# G850X.net
KiCad netlist of a schematic drawn in EAGLE
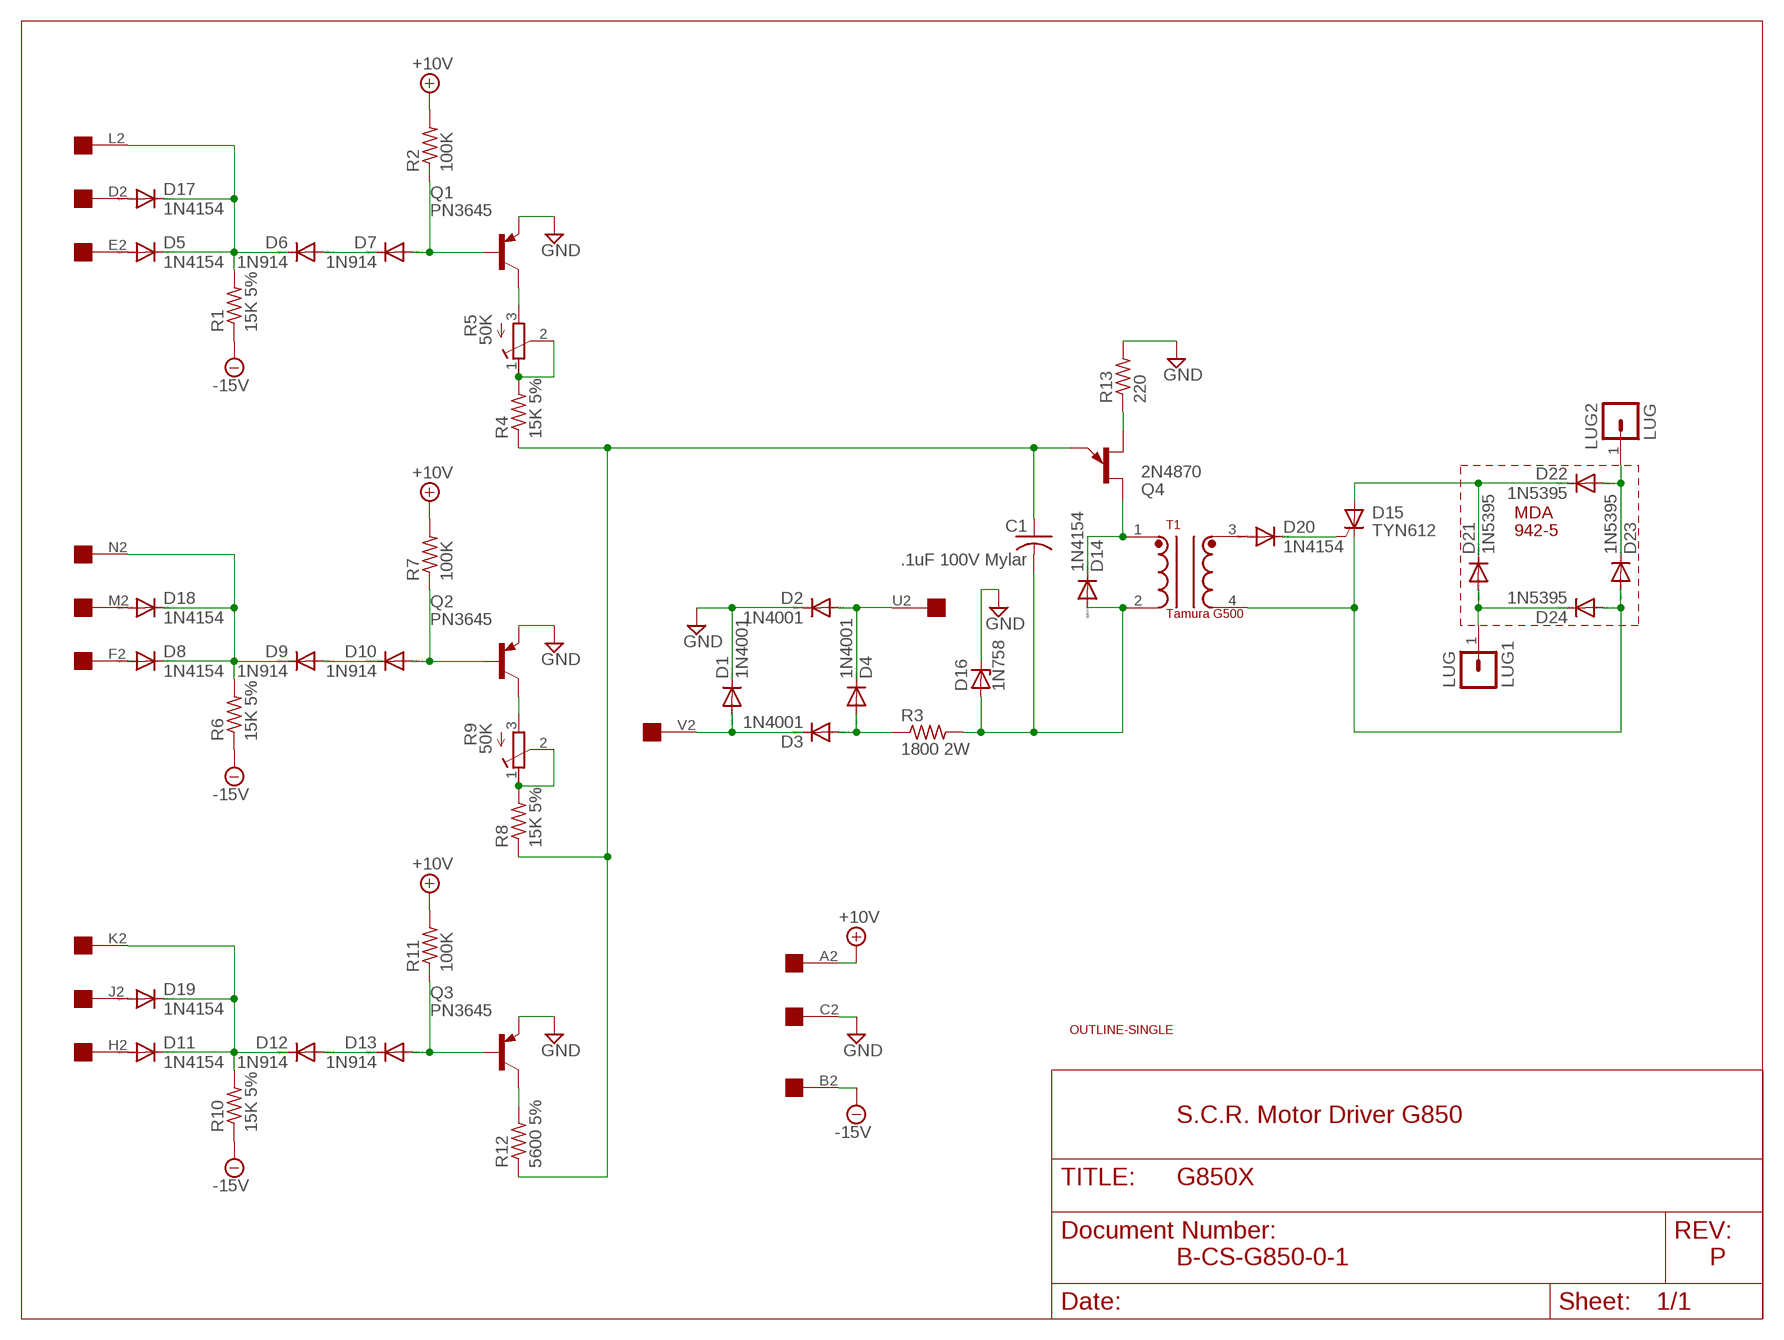
[diagram p0: schematic, sheet 1]

(export (version "E")
  (design (tool "Eeschema 10.0.6"))
  (components
    (comp (ref "C1")
      (value ".1uF 100V Mylar")
      (footprint "eagle-import:C275-093X316")
      (libsource (lib "eagle-import") (part "C-US275-093X316"))
    )
    (comp (ref "D1")
      (value "1N4001")
      (footprint "eagle-import:DO41-10")
      (libsource (lib "eagle-import") (part "1N4004"))
    )
    (comp (ref "D2")
      (value "1N4001")
      (footprint "eagle-import:DO41-10")
      (libsource (lib "eagle-import") (part "1N4004"))
    )
    (comp (ref "D3")
      (value "1N4001")
      (footprint "eagle-import:DO41-10")
      (libsource (lib "eagle-import") (part "1N4004"))
    )
    (comp (ref "D4")
      (value "1N4001")
      (footprint "eagle-import:DO41-10")
      (libsource (lib "eagle-import") (part "1N4004"))
    )
    (comp (ref "D5")
      (value "1N4154")
      (footprint "eagle-import:DO35-10")
      (libsource (lib "eagle-import") (part "1N4148DO35-10"))
    )
    (comp (ref "D6")
      (value "1N914")
      (footprint "eagle-import:DO35-10")
      (libsource (lib "eagle-import") (part "1N4148DO35-10"))
    )
    (comp (ref "D7")
      (value "1N914")
      (footprint "eagle-import:DO35-10")
      (libsource (lib "eagle-import") (part "1N4148DO35-10"))
    )
    (comp (ref "D8")
      (value "1N4154")
      (footprint "eagle-import:DO35-10")
      (libsource (lib "eagle-import") (part "1N4148DO35-10"))
    )
    (comp (ref "D9")
      (value "1N914")
      (footprint "eagle-import:DO35-10")
      (libsource (lib "eagle-import") (part "1N4148DO35-10"))
    )
    (comp (ref "D10")
      (value "1N914")
      (footprint "eagle-import:DO35-10")
      (libsource (lib "eagle-import") (part "1N4148DO35-10"))
    )
    (comp (ref "D11")
      (value "1N4154")
      (footprint "eagle-import:DO35-10")
      (libsource (lib "eagle-import") (part "1N4148DO35-10"))
    )
    (comp (ref "D12")
      (value "1N914")
      (footprint "eagle-import:DO35-10")
      (libsource (lib "eagle-import") (part "1N4148DO35-10"))
    )
    (comp (ref "D13")
      (value "1N914")
      (footprint "eagle-import:DO35-10")
      (libsource (lib "eagle-import") (part "1N4148DO35-10"))
    )
    (comp (ref "D14")
      (value "1N4154")
      (footprint "eagle-import:DO35-10")
      (libsource (lib "eagle-import") (part "1N4148DO35-10"))
    )
    (comp (ref "D15")
      (value "TYN612")
      (footprint "eagle-import:TO220CL")
      (libsource (lib "eagle-import") (part "BT151"))
    )
    (comp (ref "D16")
      (value "1N758")
      (footprint "eagle-import:DO35Z10")
      (libsource (lib "eagle-import") (part "ZENER-DIODEDO35Z10"))
    )
    (comp (ref "D17")
      (value "1N4154")
      (footprint "eagle-import:DO35-10")
      (libsource (lib "eagle-import") (part "1N4148DO35-10"))
    )
    (comp (ref "D18")
      (value "1N4154")
      (footprint "eagle-import:DO35-10")
      (libsource (lib "eagle-import") (part "1N4148DO35-10"))
    )
    (comp (ref "D19")
      (value "1N4154")
      (footprint "eagle-import:DO35-10")
      (libsource (lib "eagle-import") (part "1N4148DO35-10"))
    )
    (comp (ref "D20")
      (value "1N4154")
      (footprint "eagle-import:DO35-10")
      (libsource (lib "eagle-import") (part "1N4148DO35-10"))
    )
    (comp (ref "D21")
      (value "1N5395")
      (footprint "eagle-import:DO41-10")
      (libsource (lib "eagle-import") (part "1N4004"))
    )
    (comp (ref "D22")
      (value "1N5395")
      (footprint "eagle-import:DO41-10")
      (libsource (lib "eagle-import") (part "1N4004"))
    )
    (comp (ref "D23")
      (value "1N5395")
      (footprint "eagle-import:DO41-10")
      (libsource (lib "eagle-import") (part "1N4004"))
    )
    (comp (ref "D24")
      (value "1N5395")
      (footprint "eagle-import:DO41-10")
      (libsource (lib "eagle-import") (part "1N4004"))
    )
    (comp (ref "LUG1")
      (value "LUG")
      (footprint "eagle-import:SPADELUG")
      (libsource (lib "eagle-import") (part "LUG"))
    )
    (comp (ref "LUG2")
      (value "LUG")
      (footprint "eagle-import:SPADELUG")
      (libsource (lib "eagle-import") (part "LUG"))
    )
    (comp (ref "Q1")
      (value "PN3645")
      (footprint "eagle-import:TO39")
      (libsource (lib "eagle-import") (part "2N2904"))
    )
    (comp (ref "Q2")
      (value "PN3645")
      (footprint "eagle-import:TO39")
      (libsource (lib "eagle-import") (part "2N2904"))
    )
    (comp (ref "Q3")
      (value "PN3645")
      (footprint "eagle-import:TO39")
      (libsource (lib "eagle-import") (part "2N2904"))
    )
    (comp (ref "Q4")
      (value "2N4870")
      (footprint "eagle-import:TO72I")
      (libsource (lib "eagle-import") (part "2N2646"))
    )
    (comp (ref "R1")
      (value "15K 5%")
      (footprint "eagle-import:0207_10")
      (libsource (lib "eagle-import") (part "R-US_0207/10"))
    )
    (comp (ref "R2")
      (value "100K")
      (footprint "eagle-import:0207_10")
      (libsource (lib "eagle-import") (part "R-US_0207/10"))
    )
    (comp (ref "R3")
      (value "1800 2W")
      (footprint "eagle-import:P0817_22")
      (libsource (lib "eagle-import") (part "R-US_0817/22"))
    )
    (comp (ref "R4")
      (value "15K 5%")
      (footprint "eagle-import:0207_10")
      (libsource (lib "eagle-import") (part "R-US_0207/10"))
    )
    (comp (ref "R5")
      (value "50K")
      (footprint "eagle-import:3006Y")
      (libsource (lib "eagle-import") (part "275P"))
    )
    (comp (ref "R6")
      (value "15K 5%")
      (footprint "eagle-import:0207_10")
      (libsource (lib "eagle-import") (part "R-US_0207/10"))
    )
    (comp (ref "R7")
      (value "100K")
      (footprint "eagle-import:0207_10")
      (libsource (lib "eagle-import") (part "R-US_0207/10"))
    )
    (comp (ref "R8")
      (value "15K 5%")
      (footprint "eagle-import:0207_10")
      (libsource (lib "eagle-import") (part "R-US_0207/10"))
    )
    (comp (ref "R9")
      (value "50K")
      (footprint "eagle-import:3006Y")
      (libsource (lib "eagle-import") (part "275P"))
    )
    (comp (ref "R10")
      (value "15K 5%")
      (footprint "eagle-import:0207_10")
      (libsource (lib "eagle-import") (part "R-US_0207/10"))
    )
    (comp (ref "R11")
      (value "100K")
      (footprint "eagle-import:0207_10")
      (libsource (lib "eagle-import") (part "R-US_0207/10"))
    )
    (comp (ref "R12")
      (value "5600 5%")
      (footprint "eagle-import:0207_10")
      (libsource (lib "eagle-import") (part "R-US_0207/10"))
    )
    (comp (ref "R13")
      (value "220")
      (footprint "eagle-import:0207_10")
      (libsource (lib "eagle-import") (part "R-US_0207/10"))
    )
    (comp (ref "T1")
      (value "Tamura G500")
      (footprint "eagle-import:PT55")
      (libsource (lib "eagle-import") (part "PT55"))
    )
    (comp (ref "U$1")
      (value "OUTLINE-SINGLE")
      (footprint "eagle-import:SINGLE")
      (libsource (lib "eagle-import") (part "OUTLINE-SINGLE"))
    )
    (comp (ref "U$2")
      (value "EDGE-1")
      (footprint "eagle-import:EDGE-CON1")
      (libsource (lib "eagle-import") (part "EDGE-1"))
    )
  )
  (nets
    (net (code "1") (name "+10V") (class "Default")
      (node (ref "R11") (pin "2") (pinfunction "2_2") (pintype "passive"))
      (node (ref "R2") (pin "2") (pinfunction "2_2") (pintype "passive"))
      (node (ref "R7") (pin "2") (pinfunction "2_2") (pintype "passive"))
      (node (ref "U$2") (pin "A2") (pinfunction "1_A2") (pintype "bidirectional"))
    )
    (net (code "2") (name "-15V") (class "Default")
      (node (ref "R1") (pin "1") (pinfunction "1_1") (pintype "passive"))
      (node (ref "R10") (pin "1") (pinfunction "1_1") (pintype "passive"))
      (node (ref "R6") (pin "1") (pinfunction "1_1") (pintype "passive"))
      (node (ref "U$2") (pin "B2") (pinfunction "1_B2") (pintype "bidirectional"))
    )
    (net (code "3") (name "GND") (class "Default")
      (node (ref "D1") (pin "C") (pinfunction "C_C") (pintype "passive"))
      (node (ref "D16") (pin "C") (pinfunction "C_C") (pintype "passive"))
      (node (ref "D2") (pin "C") (pinfunction "C_C") (pintype "passive"))
      (node (ref "Q1") (pin "1") (pinfunction "E_1") (pintype "passive"))
      (node (ref "Q2") (pin "1") (pinfunction "E_1") (pintype "passive"))
      (node (ref "Q3") (pin "1") (pinfunction "E_1") (pintype "passive"))
      (node (ref "R13") (pin "2") (pinfunction "2_2") (pintype "passive"))
      (node (ref "U$2") (pin "C2") (pinfunction "1_C2") (pintype "bidirectional"))
    )
    (net (code "4") (name "Net-(C1-Pad1)") (class "Default")
      (node (ref "C1") (pin "1") (pinfunction "1_1") (pintype "passive"))
      (node (ref "Q4") (pin "E") (pinfunction "E_E") (pintype "passive"))
      (node (ref "R12") (pin "1") (pinfunction "1_1") (pintype "passive"))
      (node (ref "R4") (pin "1") (pinfunction "1_1") (pintype "passive"))
      (node (ref "R8") (pin "1") (pinfunction "1_1") (pintype "passive"))
    )
    (net (code "5") (name "Net-(D3-PadA)") (class "Default")
      (node (ref "D3") (pin "A") (pinfunction "A_A") (pintype "passive"))
      (node (ref "D4") (pin "A") (pinfunction "A_A") (pintype "passive"))
      (node (ref "R3") (pin "1") (pinfunction "1_1") (pintype "passive"))
    )
    (net (code "6") (name "Net-(D6-PadA)") (class "Default")
      (node (ref "D6") (pin "A") (pinfunction "A_A") (pintype "passive"))
      (node (ref "D7") (pin "C") (pinfunction "C_C") (pintype "passive"))
    )
    (net (code "7") (name "Net-(D10-PadC)") (class "Default")
      (node (ref "D10") (pin "C") (pinfunction "C_C") (pintype "passive"))
      (node (ref "D9") (pin "A") (pinfunction "A_A") (pintype "passive"))
    )
    (net (code "8") (name "Net-(D12-PadA)") (class "Default")
      (node (ref "D12") (pin "A") (pinfunction "A_A") (pintype "passive"))
      (node (ref "D13") (pin "C") (pinfunction "C_C") (pintype "passive"))
    )
    (net (code "9") (name "Net-(D15-PadA)") (class "Default")
      (node (ref "D15") (pin "A") (pinfunction "A_A") (pintype "passive"))
      (node (ref "D21") (pin "C") (pinfunction "C_C") (pintype "passive"))
      (node (ref "D22") (pin "C") (pinfunction "C_C") (pintype "passive"))
    )
    (net (code "10") (name "Net-(D15-PadG)") (class "Default")
      (node (ref "D15") (pin "G") (pinfunction "G_G") (pintype "passive"))
      (node (ref "D20") (pin "C") (pinfunction "C_C") (pintype "passive"))
    )
    (net (code "11") (name "Net-(D21-PadA)") (class "Default")
      (node (ref "D21") (pin "A") (pinfunction "A_A") (pintype "passive"))
      (node (ref "D24") (pin "C") (pinfunction "C_C") (pintype "passive"))
      (node (ref "LUG1") (pin "1") (pinfunction "1_1") (pintype "passive"))
    )
    (net (code "12") (name "Net-(D22-PadA)") (class "Default")
      (node (ref "D22") (pin "A") (pinfunction "A_A") (pintype "passive"))
      (node (ref "D23") (pin "C") (pinfunction "C_C") (pintype "passive"))
      (node (ref "LUG2") (pin "1") (pinfunction "1_1") (pintype "passive"))
    )
    (net (code "13") (name "Net-(Q1-B)") (class "Default")
      (node (ref "D7") (pin "A") (pinfunction "A_A") (pintype "passive"))
      (node (ref "Q1") (pin "2") (pinfunction "B_2") (pintype "passive"))
      (node (ref "R2") (pin "1") (pinfunction "1_1") (pintype "passive"))
    )
    (net (code "14") (name "Net-(Q1-C)") (class "Default")
      (node (ref "Q1") (pin "3") (pinfunction "C_3") (pintype "passive"))
      (node (ref "R5") (pin "3") (pinfunction "E_3") (pintype "passive"))
    )
    (net (code "15") (name "Net-(Q2-B)") (class "Default")
      (node (ref "D10") (pin "A") (pinfunction "A_A") (pintype "passive"))
      (node (ref "Q2") (pin "2") (pinfunction "B_2") (pintype "passive"))
      (node (ref "R7") (pin "1") (pinfunction "1_1") (pintype "passive"))
    )
    (net (code "16") (name "Net-(Q2-C)") (class "Default")
      (node (ref "Q2") (pin "3") (pinfunction "C_3") (pintype "passive"))
      (node (ref "R9") (pin "3") (pinfunction "E_3") (pintype "passive"))
    )
    (net (code "17") (name "Net-(Q3-B)") (class "Default")
      (node (ref "D13") (pin "A") (pinfunction "A_A") (pintype "passive"))
      (node (ref "Q3") (pin "2") (pinfunction "B_2") (pintype "passive"))
      (node (ref "R11") (pin "1") (pinfunction "1_1") (pintype "passive"))
    )
    (net (code "18") (name "Net-(Q3-C)") (class "Default")
      (node (ref "Q3") (pin "3") (pinfunction "C_3") (pintype "passive"))
      (node (ref "R12") (pin "2") (pinfunction "2_2") (pintype "passive"))
    )
    (net (code "19") (name "Net-(Q4-PadB1)") (class "Default")
      (node (ref "Q4") (pin "B1") (pinfunction "B1_B1") (pintype "passive"))
      (node (ref "R13") (pin "1") (pinfunction "1_1") (pintype "passive"))
    )
    (net (code "20") (name "Net-(R5-A)") (class "Default")
      (node (ref "R4") (pin "2") (pinfunction "2_2") (pintype "passive"))
      (node (ref "R5") (pin "1") (pinfunction "A_1") (pintype "passive"))
      (node (ref "R5") (pin "2") (pinfunction "S_2") (pintype "passive"))
    )
    (net (code "21") (name "Net-(R9-A)") (class "Default")
      (node (ref "R8") (pin "2") (pinfunction "2_2") (pintype "passive"))
      (node (ref "R9") (pin "1") (pinfunction "A_1") (pintype "passive"))
      (node (ref "R9") (pin "2") (pinfunction "S_2") (pintype "passive"))
    )
    (net (code "22") (name "Net-(T1-P$2)") (class "Default")
      (node (ref "D14") (pin "C") (pinfunction "C_C") (pintype "passive"))
      (node (ref "Q4") (pin "B2") (pinfunction "B2_B2") (pintype "passive"))
      (node (ref "T1") (pin "1") (pinfunction "P$2_1") (pintype "passive"))
    )
    (net (code "23") (name "Net-(T1-P$4)") (class "Default")
      (node (ref "D20") (pin "A") (pinfunction "A_A") (pintype "passive"))
      (node (ref "T1") (pin "3") (pinfunction "P$4_3") (pintype "passive"))
    )
    (net (code "24") (name "Net-(T1-P$5)") (class "Default")
      (node (ref "D15") (pin "C") (pinfunction "C_C") (pintype "passive"))
      (node (ref "D23") (pin "A") (pinfunction "A_A") (pintype "passive"))
      (node (ref "D24") (pin "A") (pinfunction "A_A") (pintype "passive"))
      (node (ref "T1") (pin "4") (pinfunction "P$5_4") (pintype "passive"))
    )
    (net (code "25") (name "Net-(T1-P$7)") (class "Default")
      (node (ref "C1") (pin "2") (pinfunction "2_2") (pintype "passive"))
      (node (ref "D14") (pin "A") (pinfunction "A_A") (pintype "passive"))
      (node (ref "D16") (pin "A") (pinfunction "A_A") (pintype "passive"))
      (node (ref "R3") (pin "2") (pinfunction "2_2") (pintype "passive"))
      (node (ref "T1") (pin "2") (pinfunction "P$7_2") (pintype "passive"))
    )
    (net (code "26") (name "Net-(U$2D-1)") (class "Default")
      (node (ref "D17") (pin "A") (pinfunction "A_A") (pintype "passive"))
      (node (ref "U$2") (pin "D2") (pinfunction "1_D2") (pintype "bidirectional"))
    )
    (net (code "27") (name "Net-(U$2E-1)") (class "Default")
      (node (ref "D5") (pin "A") (pinfunction "A_A") (pintype "passive"))
      (node (ref "U$2") (pin "E2") (pinfunction "1_E2") (pintype "bidirectional"))
    )
    (net (code "28") (name "Net-(U$2F-1)") (class "Default")
      (node (ref "D8") (pin "A") (pinfunction "A_A") (pintype "passive"))
      (node (ref "U$2") (pin "F2") (pinfunction "1_F2") (pintype "bidirectional"))
    )
    (net (code "29") (name "Net-(U$2G-1)") (class "Default")
      (node (ref "D11") (pin "A") (pinfunction "A_A") (pintype "passive"))
      (node (ref "U$2") (pin "H2") (pinfunction "1_H2") (pintype "bidirectional"))
    )
    (net (code "30") (name "Net-(U$2H-1)") (class "Default")
      (node (ref "D19") (pin "A") (pinfunction "A_A") (pintype "passive"))
      (node (ref "U$2") (pin "J2") (pinfunction "1_J2") (pintype "bidirectional"))
    )
    (net (code "31") (name "Net-(U$2I-1)") (class "Default")
      (node (ref "D11") (pin "C") (pinfunction "C_C") (pintype "passive"))
      (node (ref "D12") (pin "C") (pinfunction "C_C") (pintype "passive"))
      (node (ref "D19") (pin "C") (pinfunction "C_C") (pintype "passive"))
      (node (ref "R10") (pin "2") (pinfunction "2_2") (pintype "passive"))
      (node (ref "U$2") (pin "K2") (pinfunction "1_K2") (pintype "bidirectional"))
    )
    (net (code "32") (name "Net-(U$2J-1)") (class "Default")
      (node (ref "D17") (pin "C") (pinfunction "C_C") (pintype "passive"))
      (node (ref "D5") (pin "C") (pinfunction "C_C") (pintype "passive"))
      (node (ref "D6") (pin "C") (pinfunction "C_C") (pintype "passive"))
      (node (ref "R1") (pin "2") (pinfunction "2_2") (pintype "passive"))
      (node (ref "U$2") (pin "L2") (pinfunction "1_L2") (pintype "bidirectional"))
    )
    (net (code "33") (name "Net-(U$2K-1)") (class "Default")
      (node (ref "D18") (pin "A") (pinfunction "A_A") (pintype "passive"))
      (node (ref "U$2") (pin "M2") (pinfunction "1_M2") (pintype "bidirectional"))
    )
    (net (code "34") (name "Net-(U$2L-1)") (class "Default")
      (node (ref "D18") (pin "C") (pinfunction "C_C") (pintype "passive"))
      (node (ref "D8") (pin "C") (pinfunction "C_C") (pintype "passive"))
      (node (ref "D9") (pin "C") (pinfunction "C_C") (pintype "passive"))
      (node (ref "R6") (pin "2") (pinfunction "2_2") (pintype "passive"))
      (node (ref "U$2") (pin "N2") (pinfunction "1_N2") (pintype "bidirectional"))
    )
    (net (code "35") (name "Net-(U$2Q-1)") (class "Default")
      (node (ref "D2") (pin "A") (pinfunction "A_A") (pintype "passive"))
      (node (ref "D4") (pin "C") (pinfunction "C_C") (pintype "passive"))
      (node (ref "U$2") (pin "U2") (pinfunction "1_U2") (pintype "bidirectional"))
    )
    (net (code "36") (name "Net-(U$2R-1)") (class "Default")
      (node (ref "D1") (pin "A") (pinfunction "A_A") (pintype "passive"))
      (node (ref "D3") (pin "C") (pinfunction "C_C") (pintype "passive"))
      (node (ref "U$2") (pin "V2") (pinfunction "1_V2") (pintype "bidirectional"))
    )
  )
)
